# HC595.net
KiCad netlist of a schematic drawn in Altium Designer
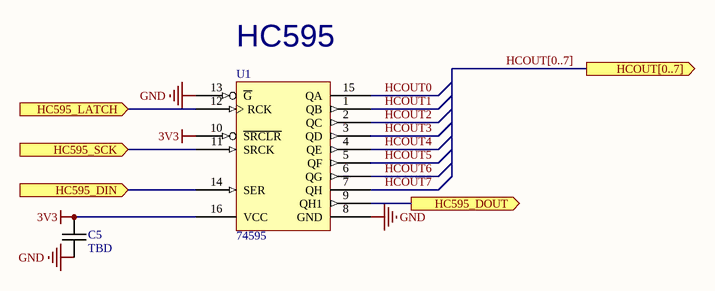
[diagram p0: HC595.SchDoc]

(export (version "E")
  (design (tool "Eeschema 10.0.6"))
  (components
    (comp (ref "C5")
      (value "TBD")
      (footprint "1210C-GENERIC")
      (description "CAPACITOR 1210 CERAMIC VALUE TO BE DETERMINED")
      (libsource (lib "RVA_Altium_Library") (part "Passives_Capacitors_1210_1210C-TBD"))
    )
    (comp (ref "U1")
      (value "74595")
      (footprint "SO16")
      (description "8-BIT SFT REG WIRTH OUTPUT LCH")
      (libsource (lib "RVA_74HC_SIPO_SMD") (part "74595"))
    )
  )
  (nets
    (net (code "1") (name "/HC595_DIN") (class "Default")
      (node (ref "U1") (pin "14") (pinfunction "SER_14") (pintype "input"))
    )
    (net (code "2") (name "/HC595_DOUT") (class "Default")
      (node (ref "U1") (pin "9") (pinfunction "QH1_9") (pintype "output"))
    )
    (net (code "3") (name "/HC595_LATCH") (class "Default")
      (node (ref "U1") (pin "12") (pinfunction "RCK_12") (pintype "input"))
    )
    (net (code "4") (name "/HC595_SCK") (class "Default")
      (node (ref "U1") (pin "11") (pinfunction "SRCK_11") (pintype "input"))
    )
    (net (code "5") (name "/HCOUT0") (class "Default")
      (node (ref "U1") (pin "15") (pinfunction "QA_15") (pintype "tri_state"))
    )
    (net (code "6") (name "/HCOUT1") (class "Default")
      (node (ref "U1") (pin "1") (pinfunction "QB_1") (pintype "output"))
    )
    (net (code "7") (name "/HCOUT2") (class "Default")
      (node (ref "U1") (pin "2") (pinfunction "QC_2") (pintype "output"))
    )
    (net (code "8") (name "/HCOUT3") (class "Default")
      (node (ref "U1") (pin "3") (pinfunction "QD_3") (pintype "output"))
    )
    (net (code "9") (name "/HCOUT4") (class "Default")
      (node (ref "U1") (pin "4") (pinfunction "QE_4") (pintype "output"))
    )
    (net (code "10") (name "/HCOUT5") (class "Default")
      (node (ref "U1") (pin "5") (pinfunction "QF_5") (pintype "output"))
    )
    (net (code "11") (name "/HCOUT6") (class "Default")
      (node (ref "U1") (pin "6") (pinfunction "QG_6") (pintype "output"))
    )
    (net (code "12") (name "/HCOUT7") (class "Default")
      (node (ref "U1") (pin "7") (pinfunction "QH_7") (pintype "tri_state"))
    )
    (net (code "14") (name "3V3") (class "Default")
      (node (ref "C5") (pin "1") (pintype "passive"))
      (node (ref "U1") (pin "10") (pinfunction "~{SRCLR}_10") (pintype "input"))
      (node (ref "U1") (pin "16") (pinfunction "VCC_16") (pintype "power_in"))
    )
    (net (code "15") (name "GND") (class "Default")
      (node (ref "C5") (pin "2") (pintype "passive"))
      (node (ref "U1") (pin "13") (pinfunction "~{G}_13") (pintype "input"))
      (node (ref "U1") (pin "8") (pinfunction "GND_8") (pintype "power_in"))
    )
  )
)
